# AL1000.net
KiCad netlist of a schematic drawn in Altium Designer
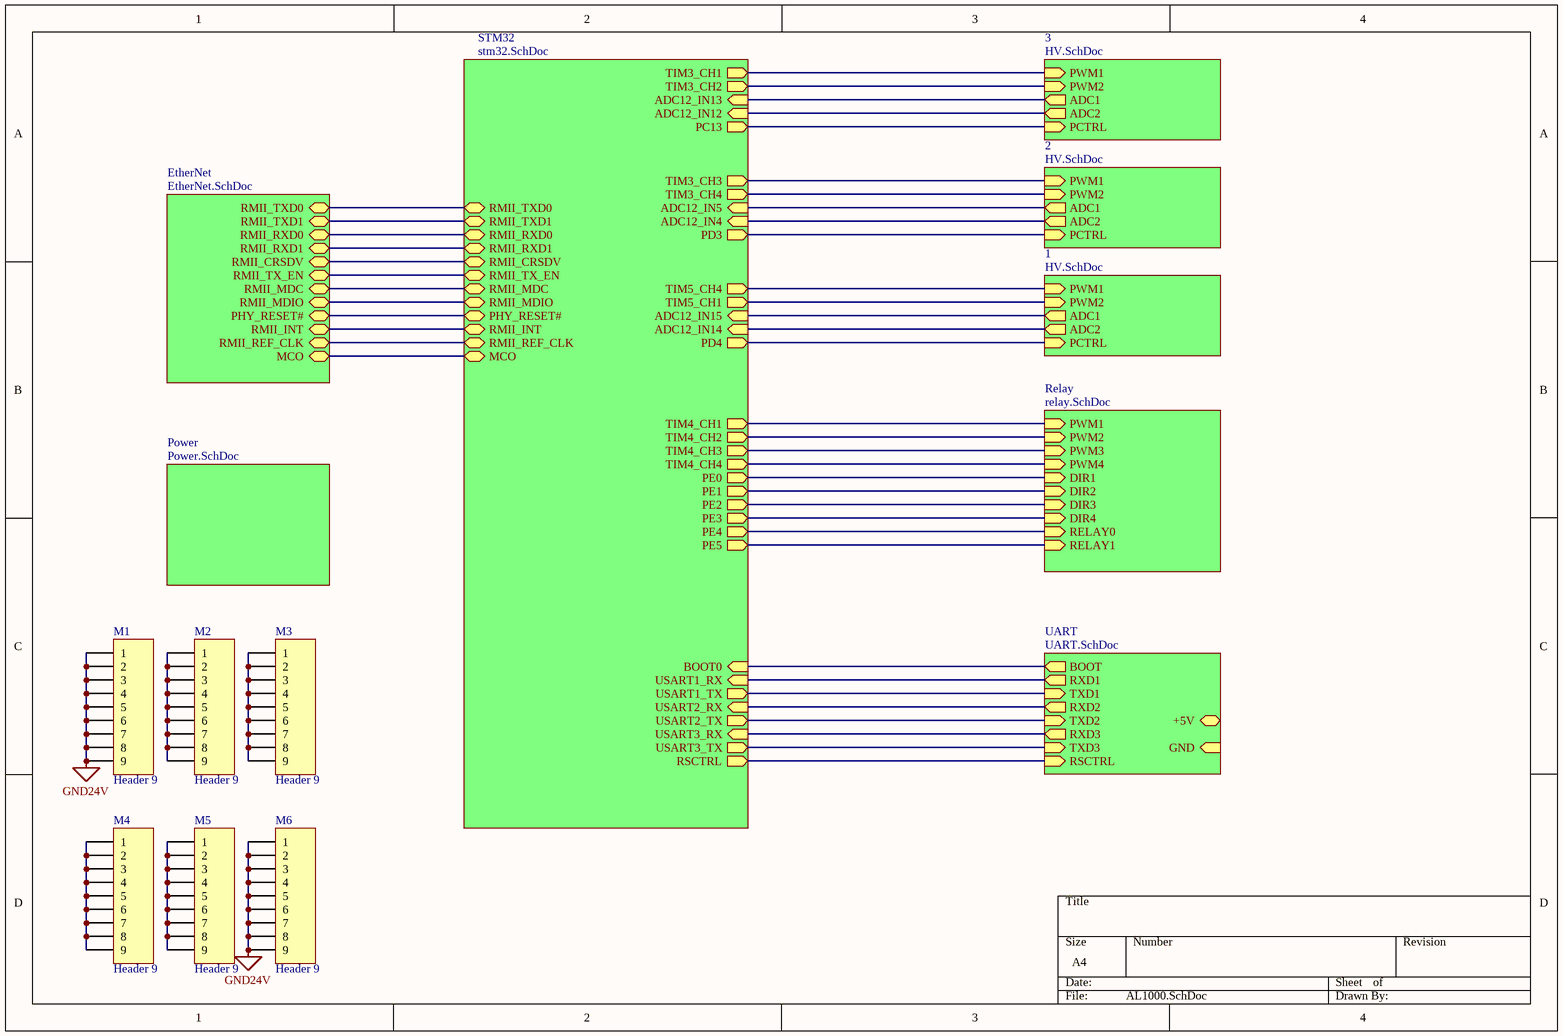
[diagram p0: AL1000.SchDoc]

(export (version "E")
  (design (tool "Eeschema 10.0.6"))
  (components
    (comp (ref "M1")
      (value "Header 9")
      (footprint "LK")
      (description "Header, 9-Pin")
      (fields (field (name "PUBLISHER") "Altium Limited"))
      (libsource (lib "Miscellaneous Connectors") (part "Header 9"))
    )
    (comp (ref "M2")
      (value "Header 9")
      (footprint "LK")
      (description "Header, 9-Pin")
      (fields (field (name "PUBLISHER") "Altium Limited"))
      (libsource (lib "Miscellaneous Connectors") (part "Header 9"))
    )
    (comp (ref "M3")
      (value "Header 9")
      (footprint "LK")
      (description "Header, 9-Pin")
      (fields (field (name "PUBLISHER") "Altium Limited"))
      (libsource (lib "Miscellaneous Connectors") (part "Header 9"))
    )
    (comp (ref "M4")
      (value "Header 9")
      (footprint "LK")
      (description "Header, 9-Pin")
      (fields (field (name "PUBLISHER") "Altium Limited"))
      (libsource (lib "Miscellaneous Connectors") (part "Header 9"))
    )
    (comp (ref "M5")
      (value "Header 9")
      (footprint "LK")
      (description "Header, 9-Pin")
      (fields (field (name "PUBLISHER") "Altium Limited"))
      (libsource (lib "Miscellaneous Connectors") (part "Header 9"))
    )
    (comp (ref "M6")
      (value "Header 9")
      (footprint "LK")
      (description "Header, 9-Pin")
      (fields (field (name "PUBLISHER") "Altium Limited"))
      (libsource (lib "Miscellaneous Connectors") (part "Header 9"))
    )
  )
  (nets
    (net (code "48") (name "GND24V") (class "Default")
      (node (ref "M1") (pin "1") (pinfunction "1_1") (pintype "passive"))
      (node (ref "M1") (pin "2") (pinfunction "2_2") (pintype "passive"))
      (node (ref "M1") (pin "3") (pinfunction "3_3") (pintype "passive"))
      (node (ref "M1") (pin "4") (pinfunction "4_4") (pintype "passive"))
      (node (ref "M1") (pin "5") (pinfunction "5_5") (pintype "passive"))
      (node (ref "M1") (pin "6") (pinfunction "6_6") (pintype "passive"))
      (node (ref "M1") (pin "7") (pinfunction "7_7") (pintype "passive"))
      (node (ref "M1") (pin "8") (pinfunction "8_8") (pintype "passive"))
      (node (ref "M1") (pin "9") (pinfunction "9_9") (pintype "passive"))
      (node (ref "M6") (pin "1") (pinfunction "1_1") (pintype "passive"))
      (node (ref "M6") (pin "2") (pinfunction "2_2") (pintype "passive"))
      (node (ref "M6") (pin "3") (pinfunction "3_3") (pintype "passive"))
      (node (ref "M6") (pin "4") (pinfunction "4_4") (pintype "passive"))
      (node (ref "M6") (pin "5") (pinfunction "5_5") (pintype "passive"))
      (node (ref "M6") (pin "6") (pinfunction "6_6") (pintype "passive"))
      (node (ref "M6") (pin "7") (pinfunction "7_7") (pintype "passive"))
      (node (ref "M6") (pin "8") (pinfunction "8_8") (pintype "passive"))
      (node (ref "M6") (pin "9") (pinfunction "9_9") (pintype "passive"))
    )
    (net (code "49") (name "Net-(M2-Pad1)") (class "Default")
      (node (ref "M2") (pin "1") (pinfunction "1_1") (pintype "passive"))
      (node (ref "M2") (pin "2") (pinfunction "2_2") (pintype "passive"))
      (node (ref "M2") (pin "3") (pinfunction "3_3") (pintype "passive"))
      (node (ref "M2") (pin "4") (pinfunction "4_4") (pintype "passive"))
      (node (ref "M2") (pin "5") (pinfunction "5_5") (pintype "passive"))
      (node (ref "M2") (pin "6") (pinfunction "6_6") (pintype "passive"))
      (node (ref "M2") (pin "7") (pinfunction "7_7") (pintype "passive"))
      (node (ref "M2") (pin "8") (pinfunction "8_8") (pintype "passive"))
      (node (ref "M2") (pin "9") (pinfunction "9_9") (pintype "passive"))
    )
    (net (code "50") (name "Net-(M3-Pad1)") (class "Default")
      (node (ref "M3") (pin "1") (pinfunction "1_1") (pintype "passive"))
      (node (ref "M3") (pin "2") (pinfunction "2_2") (pintype "passive"))
      (node (ref "M3") (pin "3") (pinfunction "3_3") (pintype "passive"))
      (node (ref "M3") (pin "4") (pinfunction "4_4") (pintype "passive"))
      (node (ref "M3") (pin "5") (pinfunction "5_5") (pintype "passive"))
      (node (ref "M3") (pin "6") (pinfunction "6_6") (pintype "passive"))
      (node (ref "M3") (pin "7") (pinfunction "7_7") (pintype "passive"))
      (node (ref "M3") (pin "8") (pinfunction "8_8") (pintype "passive"))
      (node (ref "M3") (pin "9") (pinfunction "9_9") (pintype "passive"))
    )
    (net (code "51") (name "Net-(M4-Pad1)") (class "Default")
      (node (ref "M4") (pin "1") (pinfunction "1_1") (pintype "passive"))
      (node (ref "M4") (pin "2") (pinfunction "2_2") (pintype "passive"))
      (node (ref "M4") (pin "3") (pinfunction "3_3") (pintype "passive"))
      (node (ref "M4") (pin "4") (pinfunction "4_4") (pintype "passive"))
      (node (ref "M4") (pin "5") (pinfunction "5_5") (pintype "passive"))
      (node (ref "M4") (pin "6") (pinfunction "6_6") (pintype "passive"))
      (node (ref "M4") (pin "7") (pinfunction "7_7") (pintype "passive"))
      (node (ref "M4") (pin "8") (pinfunction "8_8") (pintype "passive"))
      (node (ref "M4") (pin "9") (pinfunction "9_9") (pintype "passive"))
    )
    (net (code "52") (name "Net-(M5-Pad1)") (class "Default")
      (node (ref "M5") (pin "1") (pinfunction "1_1") (pintype "passive"))
      (node (ref "M5") (pin "2") (pinfunction "2_2") (pintype "passive"))
      (node (ref "M5") (pin "3") (pinfunction "3_3") (pintype "passive"))
      (node (ref "M5") (pin "4") (pinfunction "4_4") (pintype "passive"))
      (node (ref "M5") (pin "5") (pinfunction "5_5") (pintype "passive"))
      (node (ref "M5") (pin "6") (pinfunction "6_6") (pintype "passive"))
      (node (ref "M5") (pin "7") (pinfunction "7_7") (pintype "passive"))
      (node (ref "M5") (pin "8") (pinfunction "8_8") (pintype "passive"))
      (node (ref "M5") (pin "9") (pinfunction "9_9") (pintype "passive"))
    )
  )
)
